# iwozere.net
KiCad netlist of a schematic drawn in EAGLE
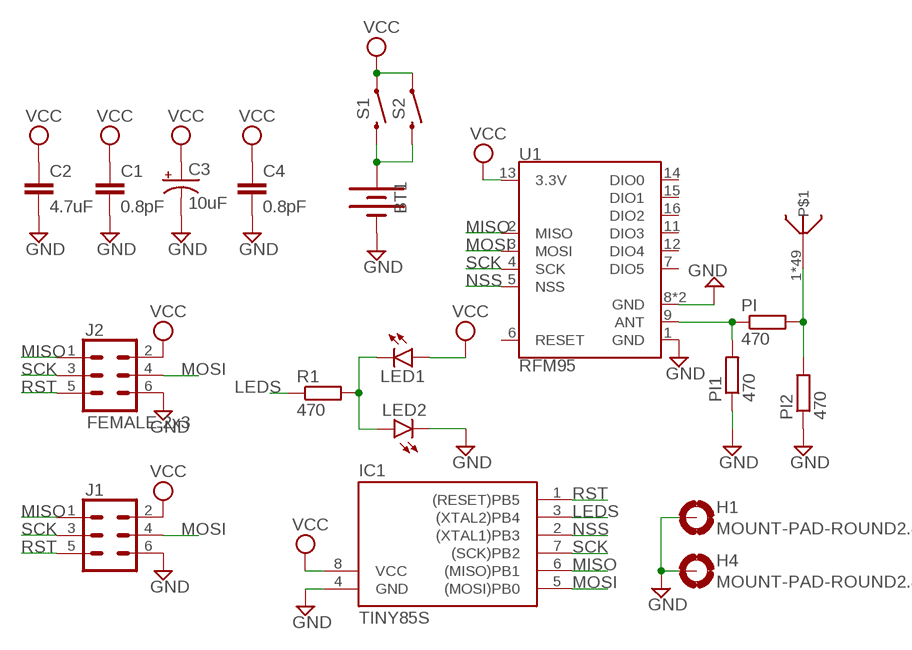
[diagram p0: schematic, sheet 1]

(export (version "E")
  (design (tool "Eeschema 10.0.6"))
  (components
    (comp (ref "BT1")
      (value "BATTERY-20MM_SMD")
      (footprint "eagle-import:BATTCON_20MM")
      (libsource (lib "eagle-import") (part "BATTERY-20MM_SMD"))
    )
    (comp (ref "C1")
      (value "0.8pF")
      (footprint "eagle-import:0402")
      (libsource (lib "eagle-import") (part "0.8PF-0402-50V-0.1PF"))
    )
    (comp (ref "C2")
      (value "4.7uF")
      (footprint "eagle-import:1206")
      (libsource (lib "eagle-import") (part "4.7UF-1206-16V-(+80/-20%)"))
    )
    (comp (ref "C3")
      (value "10uF")
      (footprint "eagle-import:CPOL-RADIAL-2.5MM-5MM")
      (libsource (lib "eagle-import") (part "10UF-POLAR-RADIAL-2.5MM-25V-20%"))
    )
    (comp (ref "C4")
      (value "0.8pF")
      (footprint "eagle-import:0402")
      (libsource (lib "eagle-import") (part "0.8PF-0402-50V-0.1PF"))
    )
    (comp (ref "H1")
      (value "MOUNT-PAD-ROUND2.8")
      (footprint "eagle-import:2,8-PAD")
      (libsource (lib "eagle-import") (part "MOUNT-PAD-ROUND2.8"))
    )
    (comp (ref "H4")
      (value "MOUNT-PAD-ROUND2.8")
      (footprint "eagle-import:2,8-PAD")
      (libsource (lib "eagle-import") (part "MOUNT-PAD-ROUND2.8"))
    )
    (comp (ref "IC1")
      (value "TINY85S")
      (footprint "eagle-import:SOIC8")
      (libsource (lib "eagle-import") (part "TINY85S"))
    )
    (comp (ref "J1")
      (value "CONN_03X2SMT")
      (footprint "eagle-import:2X3_SMT_POSTS")
      (libsource (lib "eagle-import") (part "CONN_03X2SMT"))
    )
    (comp (ref "J2")
      (value "FEMALE 2x3")
      (footprint "eagle-import:2X3")
      (libsource (lib "eagle-import") (part "CONN_03X2FEMALE"))
    )
    (comp (ref "LED1")
      (value "LEDCHIP-LED0603")
      (footprint "eagle-import:CHIP-LED0603")
      (libsource (lib "eagle-import") (part "LEDCHIP-LED0603"))
    )
    (comp (ref "LED2")
      (value "LEDCHIP-LED0603")
      (footprint "eagle-import:CHIP-LED0603")
      (libsource (lib "eagle-import") (part "LEDCHIP-LED0603"))
    )
    (comp (ref "PI")
      (value "470")
      (footprint "eagle-import:R0603")
      (libsource (lib "eagle-import") (part "R-EU_R0603"))
    )
    (comp (ref "PI1")
      (value "470")
      (footprint "eagle-import:R0603")
      (libsource (lib "eagle-import") (part "R-EU_R0603"))
    )
    (comp (ref "PI2")
      (value "470")
      (footprint "eagle-import:R0603")
      (libsource (lib "eagle-import") (part "R-EU_R0603"))
    )
    (comp (ref "R1")
      (value "470")
      (footprint "eagle-import:R0603")
      (libsource (lib "eagle-import") (part "R-EU_R0603"))
    )
    (comp (ref "S1")
      (value "MOMENTARY-SWITCH-SPST-SMD-RIGHT-ANGLE")
      (footprint "eagle-import:TACTILE_SWITCH_SMD_RIGHT_ANGLE")
      (libsource (lib "eagle-import") (part "MOMENTARY-SWITCH-SPST-SMD-RIGHT-ANGLE"))
    )
    (comp (ref "S2")
      (value "MOMENTARY-SWITCH-SPST-PTH-RIGHT-ANGLE-KIT")
      (footprint "eagle-import:TACTILE_SWITCH_PTH_RIGHT_ANGLE_KIT")
      (libsource (lib "eagle-import") (part "MOMENTARY-SWITCH-SPST-PTH-RIGHT-ANGLE-KIT"))
    )
    (comp (ref "U$1")
      (value "868MONOPOLEANTENNA")
      (footprint "eagle-import:RESC3216X70N")
      (libsource (lib "eagle-import") (part "868MONOPOLEANTENNA"))
    )
    (comp (ref "U1")
      (value "RFM95")
      (footprint "eagle-import:RFM69HCW-XXXS2")
      (libsource (lib "eagle-import") (part "RFM69HCW-915"))
    )
  )
  (nets
    (net (code "1") (name "/LEDS") (class "Default")
      (node (ref "IC1") (pin "3") (pinfunction "(XTAL2)PB4_3") (pintype "bidirectional"))
      (node (ref "R1") (pin "1") (pinfunction "1_1") (pintype "passive"))
    )
    (net (code "2") (name "/MISO") (class "Default")
      (node (ref "IC1") (pin "6") (pinfunction "(MISO)PB1_6") (pintype "bidirectional"))
      (node (ref "J1") (pin "1") (pinfunction "1_1") (pintype "bidirectional"))
      (node (ref "J2") (pin "1") (pinfunction "1_1") (pintype "bidirectional"))
      (node (ref "U1") (pin "2") (pinfunction "MISO_2") (pintype "bidirectional"))
    )
    (net (code "3") (name "/MOSI") (class "Default")
      (node (ref "IC1") (pin "5") (pinfunction "(MOSI)PB0_5") (pintype "bidirectional"))
      (node (ref "J1") (pin "4") (pinfunction "4_4") (pintype "bidirectional"))
      (node (ref "J2") (pin "4") (pinfunction "4_4") (pintype "bidirectional"))
      (node (ref "U1") (pin "3") (pinfunction "MOSI_3") (pintype "input"))
    )
    (net (code "4") (name "/NSS") (class "Default")
      (node (ref "IC1") (pin "2") (pinfunction "(XTAL1)PB3_2") (pintype "bidirectional"))
      (node (ref "U1") (pin "5") (pinfunction "NSS_5") (pintype "input"))
    )
    (net (code "5") (name "/RST") (class "Default")
      (node (ref "IC1") (pin "1") (pinfunction "(RESET)PB5_1") (pintype "bidirectional"))
      (node (ref "J1") (pin "5") (pinfunction "5_5") (pintype "bidirectional"))
      (node (ref "J2") (pin "5") (pinfunction "5_5") (pintype "bidirectional"))
    )
    (net (code "6") (name "/SCK") (class "Default")
      (node (ref "IC1") (pin "7") (pinfunction "(SCK)PB2_7") (pintype "bidirectional"))
      (node (ref "J1") (pin "3") (pinfunction "3_3") (pintype "bidirectional"))
      (node (ref "J2") (pin "3") (pinfunction "3_3") (pintype "bidirectional"))
      (node (ref "U1") (pin "4") (pinfunction "SCK_4") (pintype "input"))
    )
    (net (code "7") (name "GND") (class "Default")
      (node (ref "BT1") (pin "2") (pinfunction "-_2") (pintype "power_in"))
      (node (ref "C1") (pin "2") (pinfunction "2_2") (pintype "passive"))
      (node (ref "C2") (pin "2") (pinfunction "2_2") (pintype "passive"))
      (node (ref "C3") (pin "2") (pinfunction "-_2") (pintype "passive"))
      (node (ref "C4") (pin "2") (pinfunction "2_2") (pintype "passive"))
      (node (ref "H1") (pin "B2,8") (pinfunction "MOUNT_B2,8") (pintype "passive"))
      (node (ref "H4") (pin "B2,8") (pinfunction "MOUNT_B2,8") (pintype "passive"))
      (node (ref "IC1") (pin "4") (pinfunction "GND_4") (pintype "power_in"))
      (node (ref "J1") (pin "6") (pinfunction "6_6") (pintype "bidirectional"))
      (node (ref "J2") (pin "6") (pinfunction "6_6") (pintype "bidirectional"))
      (node (ref "LED2") (pin "C") (pinfunction "C_C") (pintype "passive"))
      (node (ref "PI1") (pin "1") (pinfunction "1_1") (pintype "passive"))
      (node (ref "PI2") (pin "1") (pinfunction "1_1") (pintype "passive"))
      (node (ref "U1") (pin "1") (pinfunction "GND_1") (pintype "power_in"))
      (node (ref "U1") (pin "10") (pinfunction "GND_10") (pintype "power_in"))
      (node (ref "U1") (pin "8") (pinfunction "GND_8") (pintype "power_in"))
    )
    (net (code "8") (name "Net-(BT1-+)") (class "Default")
      (node (ref "BT1") (pin "1") (pinfunction "+_1") (pintype "power_in"))
      (node (ref "S1") (pin "2") (pinfunction "2_2") (pintype "passive"))
      (node (ref "S2") (pin "2") (pinfunction "2_2") (pintype "passive"))
    )
    (net (code "9") (name "Net-(LED1-PadC)") (class "Default")
      (node (ref "LED1") (pin "C") (pinfunction "C_C") (pintype "passive"))
      (node (ref "LED2") (pin "A") (pinfunction "A_A") (pintype "passive"))
      (node (ref "R1") (pin "2") (pinfunction "2_2") (pintype "passive"))
    )
    (net (code "10") (name "Net-(PI-Pad2)") (class "Default")
      (node (ref "PI") (pin "2") (pinfunction "2_2") (pintype "passive"))
      (node (ref "PI2") (pin "2") (pinfunction "2_2") (pintype "passive"))
      (node (ref "U$1") (pin "1") (pinfunction "P$1_1") (pintype "bidirectional"))
      (node (ref "U$1") (pin "P$1") (pinfunction "P$1_P$1") (pintype "bidirectional"))
      (node (ref "U$1") (pin "P$10") (pinfunction "P$1_P$10") (pintype "bidirectional"))
      (node (ref "U$1") (pin "P$11") (pinfunction "P$1_P$11") (pintype "bidirectional"))
      (node (ref "U$1") (pin "P$12") (pinfunction "P$1_P$12") (pintype "bidirectional"))
      (node (ref "U$1") (pin "P$13") (pinfunction "P$1_P$13") (pintype "bidirectional"))
      (node (ref "U$1") (pin "P$14") (pinfunction "P$1_P$14") (pintype "bidirectional"))
      (node (ref "U$1") (pin "P$15") (pinfunction "P$1_P$15") (pintype "bidirectional"))
      (node (ref "U$1") (pin "P$16") (pinfunction "P$1_P$16") (pintype "bidirectional"))
      (node (ref "U$1") (pin "P$17") (pinfunction "P$1_P$17") (pintype "bidirectional"))
      (node (ref "U$1") (pin "P$18") (pinfunction "P$1_P$18") (pintype "bidirectional"))
      (node (ref "U$1") (pin "P$19") (pinfunction "P$1_P$19") (pintype "bidirectional"))
      (node (ref "U$1") (pin "P$2") (pinfunction "P$1_P$2") (pintype "bidirectional"))
      (node (ref "U$1") (pin "P$20") (pinfunction "P$1_P$20") (pintype "bidirectional"))
      (node (ref "U$1") (pin "P$21") (pinfunction "P$1_P$21") (pintype "bidirectional"))
      (node (ref "U$1") (pin "P$22") (pinfunction "P$1_P$22") (pintype "bidirectional"))
      (node (ref "U$1") (pin "P$23") (pinfunction "P$1_P$23") (pintype "bidirectional"))
      (node (ref "U$1") (pin "P$24") (pinfunction "P$1_P$24") (pintype "bidirectional"))
      (node (ref "U$1") (pin "P$25") (pinfunction "P$1_P$25") (pintype "bidirectional"))
      (node (ref "U$1") (pin "P$26") (pinfunction "P$1_P$26") (pintype "bidirectional"))
      (node (ref "U$1") (pin "P$27") (pinfunction "P$1_P$27") (pintype "bidirectional"))
      (node (ref "U$1") (pin "P$28") (pinfunction "P$1_P$28") (pintype "bidirectional"))
      (node (ref "U$1") (pin "P$29") (pinfunction "P$1_P$29") (pintype "bidirectional"))
      (node (ref "U$1") (pin "P$3") (pinfunction "P$1_P$3") (pintype "bidirectional"))
      (node (ref "U$1") (pin "P$30") (pinfunction "P$1_P$30") (pintype "bidirectional"))
      (node (ref "U$1") (pin "P$31") (pinfunction "P$1_P$31") (pintype "bidirectional"))
      (node (ref "U$1") (pin "P$32") (pinfunction "P$1_P$32") (pintype "bidirectional"))
      (node (ref "U$1") (pin "P$33") (pinfunction "P$1_P$33") (pintype "bidirectional"))
      (node (ref "U$1") (pin "P$34") (pinfunction "P$1_P$34") (pintype "bidirectional"))
      (node (ref "U$1") (pin "P$35") (pinfunction "P$1_P$35") (pintype "bidirectional"))
      (node (ref "U$1") (pin "P$36") (pinfunction "P$1_P$36") (pintype "bidirectional"))
      (node (ref "U$1") (pin "P$37") (pinfunction "P$1_P$37") (pintype "bidirectional"))
      (node (ref "U$1") (pin "P$38") (pinfunction "P$1_P$38") (pintype "bidirectional"))
      (node (ref "U$1") (pin "P$39") (pinfunction "P$1_P$39") (pintype "bidirectional"))
      (node (ref "U$1") (pin "P$4") (pinfunction "P$1_P$4") (pintype "bidirectional"))
      (node (ref "U$1") (pin "P$40") (pinfunction "P$1_P$40") (pintype "bidirectional"))
      (node (ref "U$1") (pin "P$41") (pinfunction "P$1_P$41") (pintype "bidirectional"))
      (node (ref "U$1") (pin "P$42") (pinfunction "P$1_P$42") (pintype "bidirectional"))
      (node (ref "U$1") (pin "P$43") (pinfunction "P$1_P$43") (pintype "bidirectional"))
      (node (ref "U$1") (pin "P$44") (pinfunction "P$1_P$44") (pintype "bidirectional"))
      (node (ref "U$1") (pin "P$45") (pinfunction "P$1_P$45") (pintype "bidirectional"))
      (node (ref "U$1") (pin "P$46") (pinfunction "P$1_P$46") (pintype "bidirectional"))
      (node (ref "U$1") (pin "P$47") (pinfunction "P$1_P$47") (pintype "bidirectional"))
      (node (ref "U$1") (pin "P$48") (pinfunction "P$1_P$48") (pintype "bidirectional"))
      (node (ref "U$1") (pin "P$5") (pinfunction "P$1_P$5") (pintype "bidirectional"))
      (node (ref "U$1") (pin "P$6") (pinfunction "P$1_P$6") (pintype "bidirectional"))
      (node (ref "U$1") (pin "P$7") (pinfunction "P$1_P$7") (pintype "bidirectional"))
      (node (ref "U$1") (pin "P$8") (pinfunction "P$1_P$8") (pintype "bidirectional"))
      (node (ref "U$1") (pin "P$9") (pinfunction "P$1_P$9") (pintype "bidirectional"))
    )
    (net (code "11") (name "Net-(U1-ANT)") (class "Default")
      (node (ref "PI") (pin "1") (pinfunction "1_1") (pintype "passive"))
      (node (ref "PI1") (pin "2") (pinfunction "2_2") (pintype "passive"))
      (node (ref "U1") (pin "9") (pinfunction "ANT_9") (pintype "passive"))
    )
    (net (code "12") (name "VCC") (class "Default")
      (node (ref "C1") (pin "1") (pinfunction "1_1") (pintype "passive"))
      (node (ref "C2") (pin "1") (pinfunction "1_1") (pintype "passive"))
      (node (ref "C3") (pin "1") (pinfunction "+_1") (pintype "passive"))
      (node (ref "C4") (pin "1") (pinfunction "1_1") (pintype "passive"))
      (node (ref "IC1") (pin "8") (pinfunction "VCC_8") (pintype "power_in"))
      (node (ref "J1") (pin "2") (pinfunction "2_2") (pintype "bidirectional"))
      (node (ref "J2") (pin "2") (pinfunction "2_2") (pintype "bidirectional"))
      (node (ref "LED1") (pin "A") (pinfunction "A_A") (pintype "passive"))
      (node (ref "S1") (pin "1") (pinfunction "1_1") (pintype "passive"))
      (node (ref "S2") (pin "1") (pinfunction "1_1") (pintype "passive"))
      (node (ref "U1") (pin "13") (pinfunction "3.3V_13") (pintype "power_in"))
    )
    (net (code "13") (name "unconnected-(U1-DIO0-Pad14)") (class "Default")
      (node (ref "U1") (pin "14") (pinfunction "DIO0_14") (pintype "bidirectional"))
    )
    (net (code "14") (name "unconnected-(U1-DIO1-Pad15)") (class "Default")
      (node (ref "U1") (pin "15") (pinfunction "DIO1_15") (pintype "bidirectional"))
    )
    (net (code "15") (name "unconnected-(U1-DIO2-Pad16)") (class "Default")
      (node (ref "U1") (pin "16") (pinfunction "DIO2_16") (pintype "bidirectional"))
    )
    (net (code "16") (name "unconnected-(U1-DIO3-Pad11)") (class "Default")
      (node (ref "U1") (pin "11") (pinfunction "DIO3_11") (pintype "bidirectional"))
    )
    (net (code "17") (name "unconnected-(U1-DIO4-Pad12)") (class "Default")
      (node (ref "U1") (pin "12") (pinfunction "DIO4_12") (pintype "bidirectional"))
    )
    (net (code "18") (name "unconnected-(U1-DIO5-Pad7)") (class "Default")
      (node (ref "U1") (pin "7") (pinfunction "DIO5_7") (pintype "bidirectional"))
    )
    (net (code "19") (name "unconnected-(U1-RESET-Pad6)") (class "Default")
      (node (ref "U1") (pin "6") (pinfunction "RESET_6") (pintype "input"))
    )
  )
)
